# panandtilt.net
KiCad netlist of a schematic drawn in EAGLE
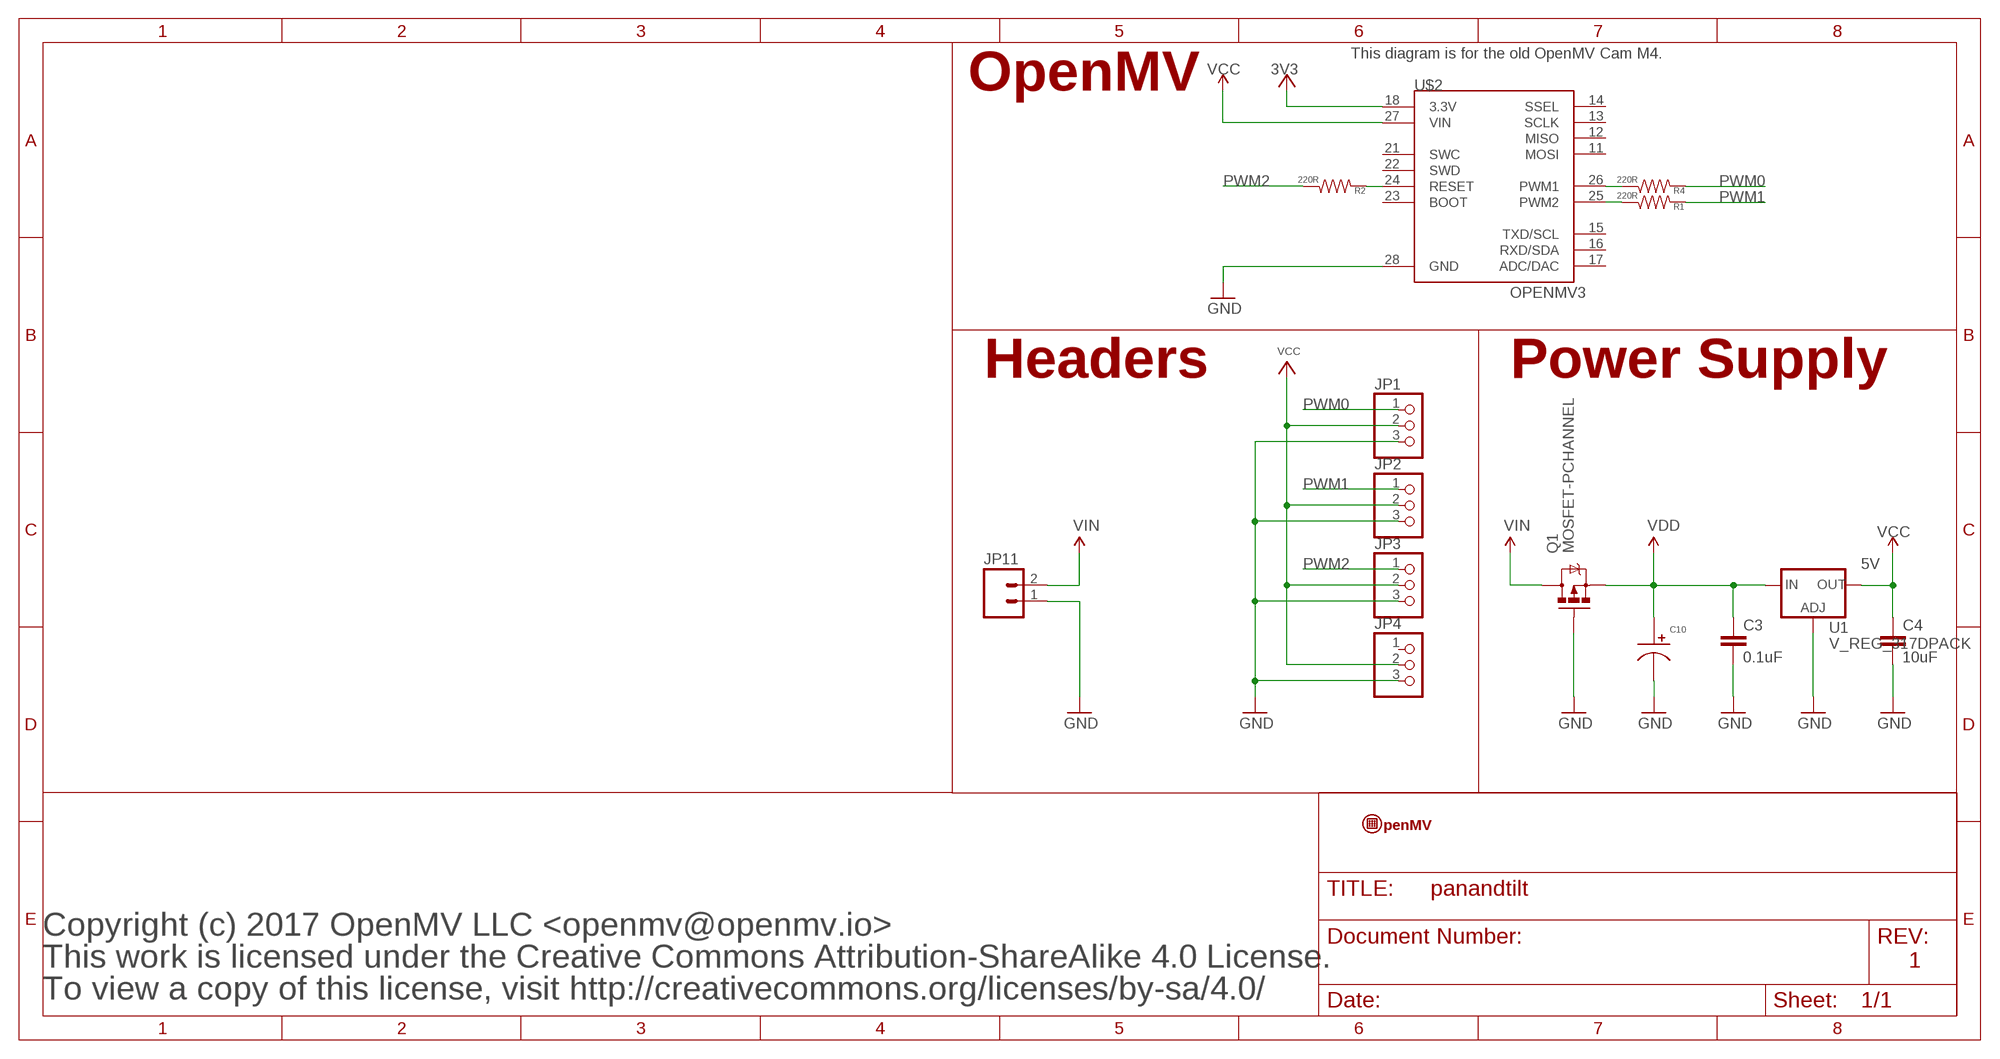
[diagram p0: schematic, sheet 1]

(export (version "E")
  (design (tool "Eeschema 10.0.6"))
  (components
    (comp (ref "C3")
      (value "0.1uF")
      (footprint "eagle-import:0603-CAP")
      (libsource (lib "eagle-import") (part "CAP0603-CAP"))
    )
    (comp (ref "C4")
      (value "10uF")
      (footprint "eagle-import:0805")
      (libsource (lib "eagle-import") (part "CAP0805"))
    )
    (comp (ref "C10")
      (value "CAPACITOR_P_10MM")
      (footprint "eagle-import:CP10MM")
      (libsource (lib "eagle-import") (part "CAPACITOR_P_10MM"))
    )
    (comp (ref "JP1")
      (value "PINHD-1X3")
      (footprint "eagle-import:1X03")
      (libsource (lib "eagle-import") (part "PINHD-1X3"))
    )
    (comp (ref "JP2")
      (value "PINHD-1X3")
      (footprint "eagle-import:1X03")
      (libsource (lib "eagle-import") (part "PINHD-1X3"))
    )
    (comp (ref "JP3")
      (value "PINHD-1X3")
      (footprint "eagle-import:1X03")
      (libsource (lib "eagle-import") (part "PINHD-1X3"))
    )
    (comp (ref "JP4")
      (value "PINHD-1X3")
      (footprint "eagle-import:1X03")
      (libsource (lib "eagle-import") (part "PINHD-1X3"))
    )
    (comp (ref "JP11")
      (value "M023.5MM")
      (footprint "eagle-import:SCREWTERMINAL-3.5MM-2")
      (libsource (lib "eagle-import") (part "M023.5MM"))
    )
    (comp (ref "Q1")
      (value "MOSFET-PCHANNEL")
      (footprint "eagle-import:SOT23-3")
      (libsource (lib "eagle-import") (part "MOSFET-PCHANNEL"))
    )
    (comp (ref "R1")
      (value "220R")
      (footprint "eagle-import:0603-RES")
      (libsource (lib "eagle-import") (part "RESISTOR0603-RES"))
    )
    (comp (ref "R2")
      (value "220R")
      (footprint "eagle-import:0603-RES")
      (libsource (lib "eagle-import") (part "RESISTOR0603-RES"))
    )
    (comp (ref "R4")
      (value "220R")
      (footprint "eagle-import:0603-RES")
      (libsource (lib "eagle-import") (part "RESISTOR0603-RES"))
    )
    (comp (ref "U$2")
      (value "OPENMV3")
      (footprint "eagle-import:OPENMV3")
      (libsource (lib "eagle-import") (part "OPENMV3"))
    )
    (comp (ref "U$9")
      (value "OPENMV-LOGO")
      (footprint "eagle-import:OPENMV-LOGO")
      (libsource (lib "eagle-import") (part "OPENMV-LOGO"))
    )
    (comp (ref "U1")
      (value "V_REG_317DPACK")
      (footprint "eagle-import:V-REG_DPACK")
      (libsource (lib "eagle-import") (part "V_REG_317DPACK"))
    )
  )
  (nets
    (net (code "1") (name "/PWM0") (class "Default")
      (node (ref "JP1") (pin "1") (pinfunction "1_1") (pintype "passive"))
      (node (ref "R4") (pin "2") (pinfunction "2_2") (pintype "passive"))
    )
    (net (code "2") (name "/PWM1") (class "Default")
      (node (ref "JP2") (pin "1") (pinfunction "1_1") (pintype "passive"))
      (node (ref "R1") (pin "2") (pinfunction "2_2") (pintype "passive"))
    )
    (net (code "3") (name "/PWM2") (class "Default")
      (node (ref "JP3") (pin "1") (pinfunction "1_1") (pintype "passive"))
      (node (ref "R2") (pin "1") (pinfunction "1_1") (pintype "passive"))
    )
    (net (code "4") (name "3V3") (class "Default")
      (node (ref "U$2") (pin "18") (pinfunction "3.3V_18") (pintype "power_in"))
    )
    (net (code "5") (name "GND") (class "Default")
      (node (ref "C10") (pin "P$2") (pinfunction "P$2_P$2") (pintype "passive"))
      (node (ref "C3") (pin "2") (pinfunction "2_2") (pintype "passive"))
      (node (ref "C4") (pin "2") (pinfunction "2_2") (pintype "passive"))
      (node (ref "JP1") (pin "3") (pinfunction "3_3") (pintype "passive"))
      (node (ref "JP11") (pin "1") (pinfunction "1_1") (pintype "passive"))
      (node (ref "JP2") (pin "3") (pinfunction "3_3") (pintype "passive"))
      (node (ref "JP3") (pin "3") (pinfunction "3_3") (pintype "passive"))
      (node (ref "JP4") (pin "3") (pinfunction "3_3") (pintype "passive"))
      (node (ref "Q1") (pin "1") (pinfunction "G_1") (pintype "passive"))
      (node (ref "U$2") (pin "28") (pinfunction "GND_28") (pintype "power_in"))
      (node (ref "U1") (pin "1") (pinfunction "ADJ_1") (pintype "input"))
    )
    (net (code "6") (name "Net-(U$2-PWM1)") (class "Default")
      (node (ref "R4") (pin "1") (pinfunction "1_1") (pintype "passive"))
      (node (ref "U$2") (pin "26") (pinfunction "PWM1_26") (pintype "bidirectional"))
    )
    (net (code "7") (name "Net-(U$2-PWM2)") (class "Default")
      (node (ref "R1") (pin "1") (pinfunction "1_1") (pintype "passive"))
      (node (ref "U$2") (pin "25") (pinfunction "PWM2_25") (pintype "bidirectional"))
    )
    (net (code "8") (name "Net-(U$2-RESET)") (class "Default")
      (node (ref "R2") (pin "2") (pinfunction "2_2") (pintype "passive"))
      (node (ref "U$2") (pin "24") (pinfunction "RESET_24") (pintype "bidirectional"))
    )
    (net (code "9") (name "VCC") (class "Default")
      (node (ref "C4") (pin "1") (pinfunction "1_1") (pintype "passive"))
      (node (ref "JP1") (pin "2") (pinfunction "2_2") (pintype "passive"))
      (node (ref "JP2") (pin "2") (pinfunction "2_2") (pintype "passive"))
      (node (ref "JP3") (pin "2") (pinfunction "2_2") (pintype "passive"))
      (node (ref "JP4") (pin "2") (pinfunction "2_2") (pintype "passive"))
      (node (ref "U$2") (pin "27") (pinfunction "VIN_27") (pintype "power_in"))
      (node (ref "U1") (pin "4") (pinfunction "OUT_4") (pintype "output"))
    )
    (net (code "10") (name "VDD") (class "Default")
      (node (ref "C10") (pin "P$1") (pinfunction "P$1_P$1") (pintype "passive"))
      (node (ref "C3") (pin "1") (pinfunction "1_1") (pintype "passive"))
      (node (ref "Q1") (pin "2") (pinfunction "S_2") (pintype "passive"))
      (node (ref "U1") (pin "3") (pinfunction "IN_3") (pintype "input"))
    )
    (net (code "11") (name "VIN") (class "Default")
      (node (ref "JP11") (pin "2") (pinfunction "2_2") (pintype "passive"))
      (node (ref "Q1") (pin "3") (pinfunction "D_3") (pintype "passive"))
    )
    (net (code "12") (name "unconnected-(JP4-Pad1)") (class "Default")
      (node (ref "JP4") (pin "1") (pinfunction "1_1") (pintype "passive"))
    )
    (net (code "13") (name "unconnected-(U$2-ADC{slash}DAC-Pad17)") (class "Default")
      (node (ref "U$2") (pin "17") (pinfunction "ADC/DAC_17") (pintype "bidirectional"))
    )
    (net (code "14") (name "unconnected-(U$2-BOOT-Pad23)") (class "Default")
      (node (ref "U$2") (pin "23") (pinfunction "BOOT_23") (pintype "bidirectional"))
    )
    (net (code "15") (name "unconnected-(U$2-MISO-Pad12)") (class "Default")
      (node (ref "U$2") (pin "12") (pinfunction "MISO_12") (pintype "bidirectional"))
    )
    (net (code "16") (name "unconnected-(U$2-MOSI-Pad11)") (class "Default")
      (node (ref "U$2") (pin "11") (pinfunction "MOSI_11") (pintype "bidirectional"))
    )
    (net (code "17") (name "unconnected-(U$2-RXD{slash}SDA-Pad16)") (class "Default")
      (node (ref "U$2") (pin "16") (pinfunction "RXD/SDA_16") (pintype "bidirectional"))
    )
    (net (code "18") (name "unconnected-(U$2-SCLK-Pad13)") (class "Default")
      (node (ref "U$2") (pin "13") (pinfunction "SCLK_13") (pintype "bidirectional"))
    )
    (net (code "19") (name "unconnected-(U$2-SSEL-Pad14)") (class "Default")
      (node (ref "U$2") (pin "14") (pinfunction "SSEL_14") (pintype "bidirectional"))
    )
    (net (code "20") (name "unconnected-(U$2-SWC-Pad21)") (class "Default")
      (node (ref "U$2") (pin "21") (pinfunction "SWC_21") (pintype "bidirectional"))
    )
    (net (code "21") (name "unconnected-(U$2-SWD-Pad22)") (class "Default")
      (node (ref "U$2") (pin "22") (pinfunction "SWD_22") (pintype "bidirectional"))
    )
    (net (code "22") (name "unconnected-(U$2-TXD{slash}SCL-Pad15)") (class "Default")
      (node (ref "U$2") (pin "15") (pinfunction "TXD/SCL_15") (pintype "bidirectional"))
    )
  )
)
